# SPEEEDuino_v1_1.net
KiCad netlist of a schematic drawn in EAGLE
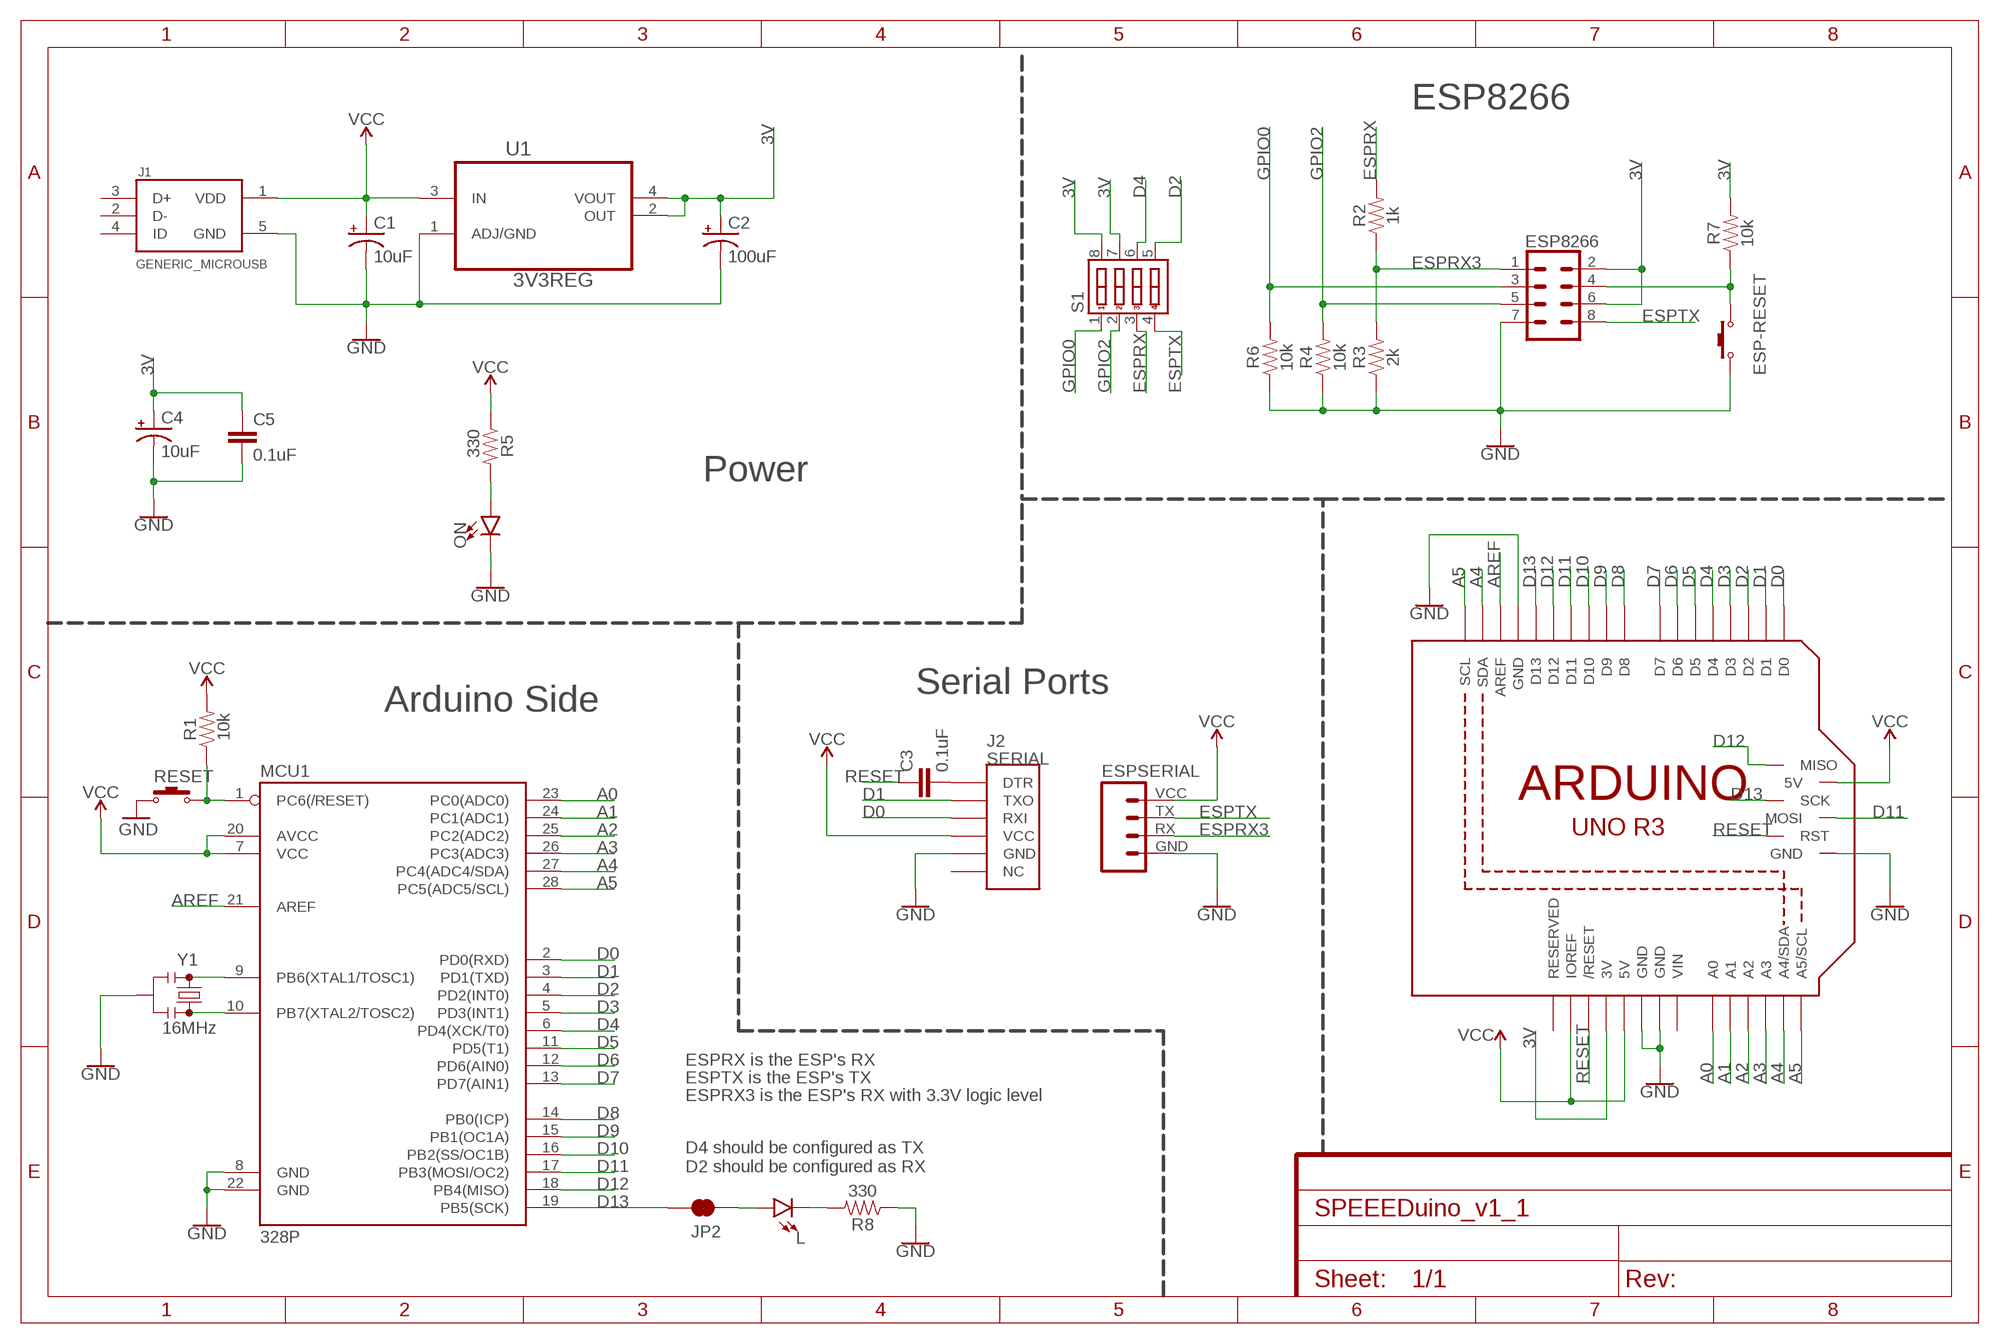
[diagram p0: schematic, sheet 1]

(export (version "E")
  (design (tool "Eeschema 10.0.6"))
  (components
    (comp (ref "C1")
      (value "10uF")
      (footprint "eagle-import:EIA3528")
      (libsource (lib "eagle-import") (part "10UF-POLAR-EIA3528-20V-10%(TANT)"))
    )
    (comp (ref "C2")
      (value "100uF")
      (footprint "eagle-import:PANASONIC_D")
      (libsource (lib "eagle-import") (part "100UF-POLAR-25V-20%(ELEC)"))
    )
    (comp (ref "C3")
      (value "0.1uF")
      (footprint "eagle-import:1206")
      (libsource (lib "eagle-import") (part "1.0UF-1206-50V-10%"))
    )
    (comp (ref "C4")
      (value "10uF")
      (footprint "eagle-import:EIA3216")
      (libsource (lib "eagle-import") (part "10UF-POLAR-EIA3216-16V-10%(TANT)"))
    )
    (comp (ref "C5")
      (value "0.1uF")
      (footprint "eagle-import:1206")
      (fields (field (name "SPICEPREFIX") "C"))
      (libsource (lib "eagle-import") (part "1.0UF-1206-50V-10%"))
    )
    (comp (ref "ESP-RESET")
      (value "SW-PB_(KAN0641)")
      (footprint "eagle-import:S-SP-4N-KAN0641")
      (fields (field (name "MF") "GANGYUAN") (field (name "MPN") "KAN0641-0501B1"))
      (libsource (lib "eagle-import") (part "SW-PB_(KAN0641)"))
    )
    (comp (ref "ESP8266")
      (value "CONN_04X2")
      (footprint "eagle-import:2X4")
      (libsource (lib "eagle-import") (part "CONN_04X2"))
    )
    (comp (ref "ESPSERIAL")
      (value "ESP8266-SERIAL0")
      (footprint "eagle-import:1X04")
      (libsource (lib "eagle-import") (part "ESP8266-SERIAL0"))
    )
    (comp (ref "J1")
      (value "GENERIC_MICROUSB")
      (footprint "eagle-import:FRAMATOME_10118194-0001LF")
      (fields (field (name "MF") "FCI") (field (name "MP") "10118194-0001LF"))
      (libsource (lib "eagle-import") (part "GENERIC_MICROUSB"))
    )
    (comp (ref "J2")
      (value "SERIAL")
      (footprint "eagle-import:CP2102_DEVICE_SIDE")
      (libsource (lib "eagle-import") (part "CP2102_DEVICECP"))
    )
    (comp (ref "JP2")
      (value "JUMPER-SMT_2_NC_TRACE_SILK")
      (footprint "eagle-import:SMT-JUMPER_2_NC_TRACE_SILK")
      (libsource (lib "eagle-import") (part "JUMPER-SMT_2_NC_TRACE_SILK"))
    )
    (comp (ref "L")
      (value "LED3MM")
      (footprint "eagle-import:LED_3MM")
      (libsource (lib "eagle-import") (part "LED3MM"))
    )
    (comp (ref "M1")
      (value "ARDUINO_R3_ICSP")
      (footprint "eagle-import:ARDUINOR3_ICSP")
      (libsource (lib "eagle-import") (part "ARDUINO_R3_ICSP"))
    )
    (comp (ref "MCU1")
      (value "328P")
      (footprint "eagle-import:DIP28")
      (libsource (lib "eagle-import") (part "ATMEGA328P_PDIP"))
    )
    (comp (ref "ON")
      (value "LED3MM")
      (footprint "eagle-import:LED_3MM")
      (libsource (lib "eagle-import") (part "LED3MM"))
    )
    (comp (ref "R1")
      (value "10k")
      (footprint "eagle-import:1206")
      (libsource (lib "eagle-import") (part "RESISTOR1206"))
    )
    (comp (ref "R2")
      (value "1k")
      (footprint "eagle-import:1206")
      (libsource (lib "eagle-import") (part "RESISTOR1206"))
    )
    (comp (ref "R3")
      (value "2k")
      (footprint "eagle-import:1206")
      (libsource (lib "eagle-import") (part "RESISTOR1206"))
    )
    (comp (ref "R4")
      (value "10k")
      (footprint "eagle-import:1206")
      (libsource (lib "eagle-import") (part "RESISTOR1206"))
    )
    (comp (ref "R5")
      (value "330")
      (footprint "eagle-import:1206")
      (libsource (lib "eagle-import") (part "RESISTOR1206"))
    )
    (comp (ref "R6")
      (value "10k")
      (footprint "eagle-import:1206")
      (libsource (lib "eagle-import") (part "RESISTOR1206"))
    )
    (comp (ref "R7")
      (value "10k")
      (footprint "eagle-import:1206")
      (libsource (lib "eagle-import") (part "RESISTOR1206"))
    )
    (comp (ref "R8")
      (value "330")
      (footprint "eagle-import:1206")
      (libsource (lib "eagle-import") (part "RESISTOR1206"))
    )
    (comp (ref "RESET")
      (value "SW-PB_(KAN0641)")
      (footprint "eagle-import:S-SP-4N-KAN0641")
      (fields (field (name "MF") "GANGYUAN") (field (name "MPN") "KAN0641-0501B1"))
      (libsource (lib "eagle-import") (part "SW-PB_(KAN0641)"))
    )
    (comp (ref "S1")
      (value "4 WAYS")
      (footprint "eagle-import:SW-DIP-4-SMD")
      (libsource (lib "eagle-import") (part "SW-DIP-4_(SW-DIP-4-SMD)"))
    )
    (comp (ref "U1")
      (value "3V3REG")
      (footprint "eagle-import:SOT230P696X180-4N")
      (fields (field (name "MPN") "LM1117MP-3.3"))
      (libsource (lib "eagle-import") (part "LM1117MP-3.3"))
    )
    (comp (ref "Y1")
      (value "16MHz")
      (footprint "eagle-import:RESONATOR-SMD-3.2X1.3")
      (libsource (lib "eagle-import") (part "RESONATOR-16MHZSMD_3.2X1.3"))
    )
  )
  (nets
    (net (code "1") (name "/3V") (class "Default")
      (node (ref "C2") (pin "+") (pinfunction "+_+") (pintype "passive"))
      (node (ref "C4") (pin "+") (pinfunction "+_+") (pintype "passive"))
      (node (ref "C5") (pin "1") (pinfunction "1_1") (pintype "passive"))
      (node (ref "ESP8266") (pin "2") (pinfunction "2_2") (pintype "passive"))
      (node (ref "ESP8266") (pin "6") (pinfunction "6_6") (pintype "passive"))
      (node (ref "M1") (pin "3V") (pinfunction "3V_3V") (pintype "power_in"))
      (node (ref "R7") (pin "2") (pinfunction "2_2") (pintype "passive"))
      (node (ref "S1") (pin "7") (pinfunction "P$7_7") (pintype "bidirectional"))
      (node (ref "S1") (pin "8") (pinfunction "P$8_8") (pintype "bidirectional"))
      (node (ref "U1") (pin "2") (pinfunction "OUT_2") (pintype "output"))
      (node (ref "U1") (pin "4") (pinfunction "VOUT_4") (pintype "output"))
    )
    (net (code "2") (name "/A0") (class "Default")
      (node (ref "M1") (pin "A0") (pinfunction "A0_A0") (pintype "bidirectional"))
      (node (ref "MCU1") (pin "23") (pinfunction "PC0(ADC0)_23") (pintype "bidirectional"))
    )
    (net (code "3") (name "/A1") (class "Default")
      (node (ref "M1") (pin "A1") (pinfunction "A1_A1") (pintype "bidirectional"))
      (node (ref "MCU1") (pin "24") (pinfunction "PC1(ADC1)_24") (pintype "bidirectional"))
    )
    (net (code "4") (name "/A2") (class "Default")
      (node (ref "M1") (pin "A2") (pinfunction "A2_A2") (pintype "bidirectional"))
      (node (ref "MCU1") (pin "25") (pinfunction "PC2(ADC2)_25") (pintype "bidirectional"))
    )
    (net (code "5") (name "/A3") (class "Default")
      (node (ref "M1") (pin "A3") (pinfunction "A3_A3") (pintype "bidirectional"))
      (node (ref "MCU1") (pin "26") (pinfunction "PC3(ADC3)_26") (pintype "bidirectional"))
    )
    (net (code "6") (name "/A4") (class "Default")
      (node (ref "M1") (pin "A4") (pinfunction "A4/SDA_A4") (pintype "bidirectional"))
      (node (ref "M1") (pin "SDA") (pinfunction "SDA_SDA") (pintype "bidirectional"))
      (node (ref "MCU1") (pin "27") (pinfunction "PC4(ADC4/SDA)_27") (pintype "bidirectional"))
    )
    (net (code "7") (name "/A5") (class "Default")
      (node (ref "M1") (pin "A5") (pinfunction "A5/SCL_A5") (pintype "bidirectional"))
      (node (ref "M1") (pin "SCL") (pinfunction "SCL_SCL") (pintype "bidirectional"))
      (node (ref "MCU1") (pin "28") (pinfunction "PC5(ADC5/SCL)_28") (pintype "bidirectional"))
    )
    (net (code "8") (name "/AREF") (class "Default")
      (node (ref "M1") (pin "AREF") (pinfunction "AREF_AREF") (pintype "bidirectional"))
      (node (ref "MCU1") (pin "21") (pinfunction "AREF_21") (pintype "bidirectional"))
    )
    (net (code "9") (name "/D0") (class "Default")
      (node (ref "J2") (pin "P$3") (pinfunction "RXI_P$3") (pintype "bidirectional"))
      (node (ref "M1") (pin "D0") (pinfunction "D0_D0") (pintype "bidirectional"))
      (node (ref "MCU1") (pin "2") (pinfunction "PD0(RXD)_2") (pintype "bidirectional"))
    )
    (net (code "10") (name "/D1") (class "Default")
      (node (ref "J2") (pin "P$2") (pinfunction "TXO_P$2") (pintype "bidirectional"))
      (node (ref "M1") (pin "D1") (pinfunction "D1_D1") (pintype "bidirectional"))
      (node (ref "MCU1") (pin "3") (pinfunction "PD1(TXD)_3") (pintype "bidirectional"))
    )
    (net (code "11") (name "/D2") (class "Default")
      (node (ref "M1") (pin "D2") (pinfunction "D2_D2") (pintype "bidirectional"))
      (node (ref "MCU1") (pin "4") (pinfunction "PD2(INT0)_4") (pintype "bidirectional"))
      (node (ref "S1") (pin "5") (pinfunction "P$5_5") (pintype "bidirectional"))
    )
    (net (code "12") (name "/D3") (class "Default")
      (node (ref "M1") (pin "D3") (pinfunction "D3_D3") (pintype "bidirectional"))
      (node (ref "MCU1") (pin "5") (pinfunction "PD3(INT1)_5") (pintype "bidirectional"))
    )
    (net (code "13") (name "/D4") (class "Default")
      (node (ref "M1") (pin "D4") (pinfunction "D4_D4") (pintype "bidirectional"))
      (node (ref "MCU1") (pin "6") (pinfunction "PD4(XCK/T0)_6") (pintype "bidirectional"))
      (node (ref "S1") (pin "6") (pinfunction "P$6_6") (pintype "bidirectional"))
    )
    (net (code "14") (name "/D5") (class "Default")
      (node (ref "M1") (pin "D5") (pinfunction "D5_D5") (pintype "bidirectional"))
      (node (ref "MCU1") (pin "11") (pinfunction "PD5(T1)_11") (pintype "bidirectional"))
    )
    (net (code "15") (name "/D6") (class "Default")
      (node (ref "M1") (pin "D6") (pinfunction "D6_D6") (pintype "bidirectional"))
      (node (ref "MCU1") (pin "12") (pinfunction "PD6(AIN0)_12") (pintype "bidirectional"))
    )
    (net (code "16") (name "/D7") (class "Default")
      (node (ref "M1") (pin "D7") (pinfunction "D7_D7") (pintype "bidirectional"))
      (node (ref "MCU1") (pin "13") (pinfunction "PD7(AIN1)_13") (pintype "bidirectional"))
    )
    (net (code "17") (name "/D8") (class "Default")
      (node (ref "M1") (pin "D8") (pinfunction "D8_D8") (pintype "bidirectional"))
      (node (ref "MCU1") (pin "14") (pinfunction "PB0(ICP)_14") (pintype "bidirectional"))
    )
    (net (code "18") (name "/D9") (class "Default")
      (node (ref "M1") (pin "D9") (pinfunction "D9_D9") (pintype "bidirectional"))
      (node (ref "MCU1") (pin "15") (pinfunction "PB1(OC1A)_15") (pintype "bidirectional"))
    )
    (net (code "19") (name "/D10") (class "Default")
      (node (ref "M1") (pin "D10") (pinfunction "D10_D10") (pintype "bidirectional"))
      (node (ref "MCU1") (pin "16") (pinfunction "PB2(SS/OC1B)_16") (pintype "bidirectional"))
    )
    (net (code "20") (name "/D11") (class "Default")
      (node (ref "M1") (pin "D11") (pinfunction "D11_D11") (pintype "bidirectional"))
      (node (ref "M1") (pin "MOSI") (pinfunction "MOSI_MOSI") (pintype "passive"))
      (node (ref "MCU1") (pin "17") (pinfunction "PB3(MOSI/OC2)_17") (pintype "bidirectional"))
    )
    (net (code "21") (name "/D12") (class "Default")
      (node (ref "M1") (pin "D12") (pinfunction "D12_D12") (pintype "bidirectional"))
      (node (ref "M1") (pin "MISO") (pinfunction "MISO_MISO") (pintype "passive"))
      (node (ref "MCU1") (pin "18") (pinfunction "PB4(MISO)_18") (pintype "bidirectional"))
    )
    (net (code "22") (name "/D13") (class "Default")
      (node (ref "JP2") (pin "2") (pinfunction "2_2") (pintype "passive"))
      (node (ref "M1") (pin "D13") (pinfunction "D13_D13") (pintype "bidirectional"))
      (node (ref "M1") (pin "SCK") (pinfunction "SCK_SCK") (pintype "passive"))
      (node (ref "MCU1") (pin "19") (pinfunction "PB5(SCK)_19") (pintype "bidirectional"))
    )
    (net (code "23") (name "/ESPRX") (class "Default")
      (node (ref "R2") (pin "2") (pinfunction "2_2") (pintype "passive"))
      (node (ref "S1") (pin "3") (pinfunction "P$3_3") (pintype "bidirectional"))
    )
    (net (code "24") (name "/ESPRX3") (class "Default")
      (node (ref "ESP8266") (pin "1") (pinfunction "1_1") (pintype "passive"))
      (node (ref "ESPSERIAL") (pin "RX") (pinfunction "TX_RX") (pintype "passive"))
      (node (ref "R2") (pin "1") (pinfunction "1_1") (pintype "passive"))
      (node (ref "R3") (pin "2") (pinfunction "2_2") (pintype "passive"))
    )
    (net (code "25") (name "/ESPTX") (class "Default")
      (node (ref "ESP8266") (pin "8") (pinfunction "8_8") (pintype "passive"))
      (node (ref "ESPSERIAL") (pin "TX") (pinfunction "RX_TX") (pintype "passive"))
      (node (ref "S1") (pin "4") (pinfunction "P$4_4") (pintype "bidirectional"))
    )
    (net (code "26") (name "/GPIO0") (class "Default")
      (node (ref "ESP8266") (pin "3") (pinfunction "3_3") (pintype "passive"))
      (node (ref "R6") (pin "2") (pinfunction "2_2") (pintype "passive"))
      (node (ref "S1") (pin "1") (pinfunction "P$1_1") (pintype "bidirectional"))
    )
    (net (code "27") (name "/GPIO2") (class "Default")
      (node (ref "ESP8266") (pin "5") (pinfunction "5_5") (pintype "passive"))
      (node (ref "R4") (pin "2") (pinfunction "2_2") (pintype "passive"))
      (node (ref "S1") (pin "2") (pinfunction "P$2_2") (pintype "bidirectional"))
    )
    (net (code "28") (name "/RESET") (class "Default")
      (node (ref "C3") (pin "1") (pinfunction "1_1") (pintype "passive"))
      (node (ref "M1") (pin "RESET") (pinfunction "/RESET_RESET") (pintype "bidirectional"))
      (node (ref "M1") (pin "RESET_ICSP") (pinfunction "RST_RESET_ICSP") (pintype "passive"))
      (node (ref "MCU1") (pin "1") (pinfunction "PC6(/RESET)_1") (pintype "bidirectional"))
      (node (ref "R1") (pin "1") (pinfunction "1_1") (pintype "passive"))
      (node (ref "RESET") (pin "3") (pinfunction "2_3") (pintype "passive"))
      (node (ref "RESET") (pin "4") (pinfunction "2_4") (pintype "passive"))
    )
    (net (code "29") (name "/VIN") (class "Default")
      (node (ref "M1") (pin "VIN") (pinfunction "VIN_VIN") (pintype "power_in"))
    )
    (net (code "30") (name "GND") (class "Default")
      (node (ref "C1") (pin "C") (pinfunction "-_C") (pintype "passive"))
      (node (ref "C2") (pin "-") (pinfunction "-_-") (pintype "passive"))
      (node (ref "C4") (pin "-") (pinfunction "-_-") (pintype "passive"))
      (node (ref "C5") (pin "2") (pinfunction "2_2") (pintype "passive"))
      (node (ref "ESP-RESET") (pin "1") (pinfunction "1_1") (pintype "passive"))
      (node (ref "ESP-RESET") (pin "2") (pinfunction "1_2") (pintype "passive"))
      (node (ref "ESP8266") (pin "7") (pinfunction "7_7") (pintype "passive"))
      (node (ref "ESPSERIAL") (pin "GND") (pinfunction "VCC_GND") (pintype "passive"))
      (node (ref "J1") (pin "5") (pinfunction "GND_5") (pintype "power_in"))
      (node (ref "J2") (pin "P$5") (pinfunction "GND_P$5") (pintype "bidirectional"))
      (node (ref "M1") (pin "GND") (pinfunction "GND_GND") (pintype "power_in"))
      (node (ref "M1") (pin "GND@1") (pinfunction "GND_GND@1") (pintype "power_in"))
      (node (ref "M1") (pin "GND@2") (pinfunction "GND_GND@2") (pintype "passive"))
      (node (ref "M1") (pin "GND@3") (pinfunction "GND_GND@3") (pintype "power_in"))
      (node (ref "MCU1") (pin "22") (pinfunction "GND_22") (pintype "bidirectional"))
      (node (ref "MCU1") (pin "8") (pinfunction "GND_8") (pintype "bidirectional"))
      (node (ref "ON") (pin "K") (pinfunction "C_K") (pintype "passive"))
      (node (ref "R3") (pin "1") (pinfunction "1_1") (pintype "passive"))
      (node (ref "R4") (pin "1") (pinfunction "1_1") (pintype "passive"))
      (node (ref "R6") (pin "1") (pinfunction "1_1") (pintype "passive"))
      (node (ref "R8") (pin "1") (pinfunction "1_1") (pintype "passive"))
      (node (ref "RESET") (pin "1") (pinfunction "1_1") (pintype "passive"))
      (node (ref "RESET") (pin "2") (pinfunction "1_2") (pintype "passive"))
      (node (ref "U1") (pin "1") (pinfunction "ADJ/GND_1") (pintype "passive"))
      (node (ref "Y1") (pin "2") (pinfunction "2_2") (pintype "passive"))
    )
    (net (code "31") (name "Net-(ESP-RESET-2-Pad3)") (class "Default")
      (node (ref "ESP-RESET") (pin "3") (pinfunction "2_3") (pintype "passive"))
      (node (ref "ESP-RESET") (pin "4") (pinfunction "2_4") (pintype "passive"))
      (node (ref "ESP8266") (pin "4") (pinfunction "4_4") (pintype "passive"))
      (node (ref "R7") (pin "1") (pinfunction "1_1") (pintype "passive"))
    )
    (net (code "32") (name "Net-(J2-DTR)") (class "Default")
      (node (ref "C3") (pin "2") (pinfunction "2_2") (pintype "passive"))
      (node (ref "J2") (pin "P$1") (pinfunction "DTR_P$1") (pintype "bidirectional"))
    )
    (net (code "33") (name "Net-(JP2-Pad1)") (class "Default")
      (node (ref "JP2") (pin "1") (pinfunction "1_1") (pintype "passive"))
      (node (ref "L") (pin "A") (pinfunction "A_A") (pintype "passive"))
    )
    (net (code "34") (name "Net-(L-C)") (class "Default")
      (node (ref "L") (pin "K") (pinfunction "C_K") (pintype "passive"))
      (node (ref "R8") (pin "2") (pinfunction "2_2") (pintype "passive"))
    )
    (net (code "35") (name "Net-(MCU1-PB6(XTAL1{slash}TOSC1))") (class "Default")
      (node (ref "MCU1") (pin "9") (pinfunction "PB6(XTAL1/TOSC1)_9") (pintype "bidirectional"))
      (node (ref "Y1") (pin "1") (pinfunction "1_1") (pintype "passive"))
    )
    (net (code "36") (name "Net-(MCU1-PB7(XTAL2{slash}TOSC2))") (class "Default")
      (node (ref "MCU1") (pin "10") (pinfunction "PB7(XTAL2/TOSC2)_10") (pintype "bidirectional"))
      (node (ref "Y1") (pin "3") (pinfunction "3_3") (pintype "passive"))
    )
    (net (code "37") (name "Net-(ON-PadA)") (class "Default")
      (node (ref "ON") (pin "A") (pinfunction "A_A") (pintype "passive"))
      (node (ref "R5") (pin "2") (pinfunction "2_2") (pintype "passive"))
    )
    (net (code "38") (name "VCC") (class "Default")
      (node (ref "C1") (pin "A") (pinfunction "+_A") (pintype "passive"))
      (node (ref "ESPSERIAL") (pin "VCC") (pinfunction "GND_VCC") (pintype "passive"))
      (node (ref "J1") (pin "1") (pinfunction "VDD_1") (pintype "power_in"))
      (node (ref "J2") (pin "P$4") (pinfunction "VCC_P$4") (pintype "bidirectional"))
      (node (ref "M1") (pin "5V") (pinfunction "5V_5V") (pintype "power_in"))
      (node (ref "M1") (pin "5V_ICSP") (pinfunction "5V_5V_ICSP") (pintype "passive"))
      (node (ref "M1") (pin "IOREF") (pinfunction "IOREF_IOREF") (pintype "output"))
      (node (ref "MCU1") (pin "20") (pinfunction "AVCC_20") (pintype "bidirectional"))
      (node (ref "MCU1") (pin "7") (pinfunction "VCC_7") (pintype "bidirectional"))
      (node (ref "R1") (pin "2") (pinfunction "2_2") (pintype "passive"))
      (node (ref "R5") (pin "1") (pinfunction "1_1") (pintype "passive"))
      (node (ref "U1") (pin "3") (pinfunction "IN_3") (pintype "input"))
    )
    (net (code "39") (name "unconnected-(J1-D+-Pad3)") (class "Default")
      (node (ref "J1") (pin "3") (pinfunction "D+_3") (pintype "bidirectional"))
    )
    (net (code "40") (name "unconnected-(J1-D--Pad2)") (class "Default")
      (node (ref "J1") (pin "2") (pinfunction "D-_2") (pintype "bidirectional"))
    )
    (net (code "41") (name "unconnected-(J1-ID-Pad4)") (class "Default")
      (node (ref "J1") (pin "4") (pinfunction "ID_4") (pintype "passive"))
    )
    (net (code "42") (name "unconnected-(J2-NC-PadP$6)") (class "Default")
      (node (ref "J2") (pin "P$6") (pinfunction "NC_P$6") (pintype "bidirectional"))
    )
    (net (code "43") (name "unconnected-(M1-PadRESERVED)") (class "Default")
      (node (ref "M1") (pin "RESERVED") (pinfunction "RESERVED_RESERVED") (pintype "no_connect"))
    )
  )
)
